# Grove_-_BLE_v1_0.net
KiCad netlist of a schematic drawn in EAGLE
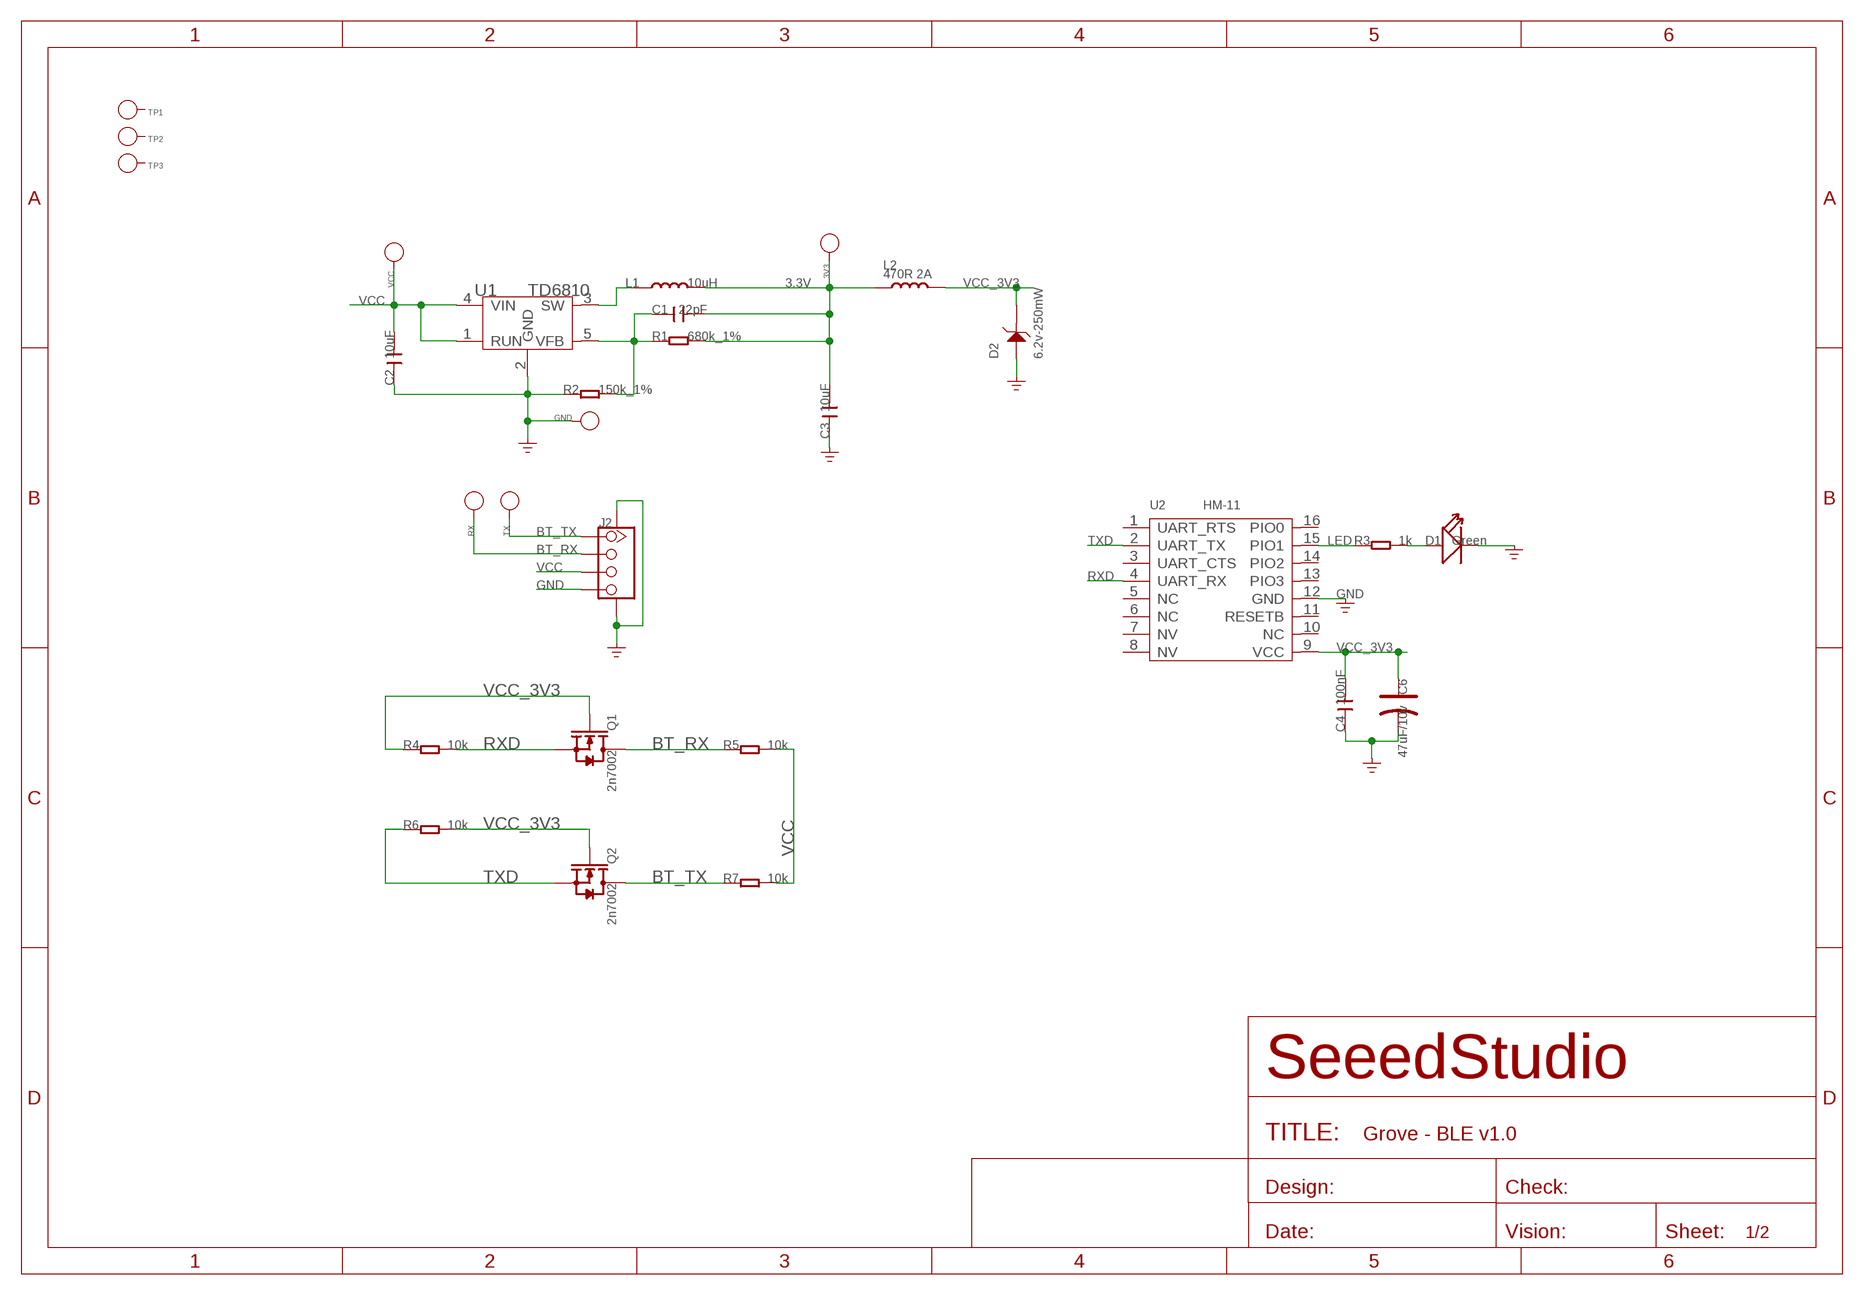
[diagram p0: schematic, sheet 1]
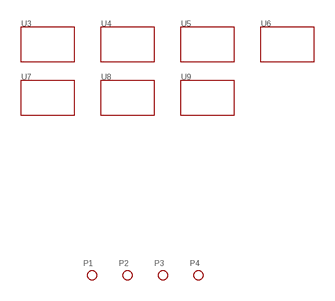
[diagram p1: schematic, sheet 2]

(export (version "E")
  (design (tool "Eeschema 10.0.6"))
  (components
    (comp (ref "P1")
      (value "PAD-MARK")
      (footprint "eagle-import:ROUND-MARK-1.0")
      (fields (field (name "PARTNO") "DNP"))
      (libsource (lib "eagle-import") (part "PAD-MARK"))
    )
    (comp (ref "P2")
      (value "PAD-MARK")
      (footprint "eagle-import:ROUND-MARK-1.0")
      (fields (field (name "PARTNO") "DNP"))
      (libsource (lib "eagle-import") (part "PAD-MARK"))
    )
    (comp (ref "P3")
      (value "PAD-MARK")
      (footprint "eagle-import:ROUND-MARK-1.0")
      (fields (field (name "PARTNO") "DNP"))
      (libsource (lib "eagle-import") (part "PAD-MARK"))
    )
    (comp (ref "P4")
      (value "PAD-MARK")
      (footprint "eagle-import:ROUND-MARK-1.0")
      (fields (field (name "PARTNO") "DNP"))
      (libsource (lib "eagle-import") (part "PAD-MARK"))
    )
    (comp (ref "U3")
      (value "TWIG'2U'")
      (footprint "eagle-import:GROVE-TEST-PLATFORM")
      (libsource (lib "eagle-import") (part "TWIG'2U'"))
    )
    (comp (ref "U4")
      (value "TWIG'2U'")
      (footprint "eagle-import:GROVE-TEST-PLATFORM")
      (libsource (lib "eagle-import") (part "TWIG'2U'"))
    )
    (comp (ref "U5")
      (value "TWIG'2U'")
      (footprint "eagle-import:GROVE-TEST-PLATFORM")
      (libsource (lib "eagle-import") (part "TWIG'2U'"))
    )
    (comp (ref "U6")
      (value "TWIG'2U'")
      (footprint "eagle-import:GROVE-TEST-PLATFORM")
      (libsource (lib "eagle-import") (part "TWIG'2U'"))
    )
    (comp (ref "U7")
      (value "TWIG'2U'")
      (footprint "eagle-import:GROVE-TEST-PLATFORM")
      (libsource (lib "eagle-import") (part "TWIG'2U'"))
    )
    (comp (ref "U8")
      (value "TWIG'2U'")
      (footprint "eagle-import:GROVE-TEST-PLATFORM")
      (libsource (lib "eagle-import") (part "TWIG'2U'"))
    )
    (comp (ref "U9")
      (value "TWIG'2U'")
      (footprint "eagle-import:GROVE-TEST-PLATFORM")
      (libsource (lib "eagle-import") (part "TWIG'2U'"))
    )
    (comp (ref "3V3")
      (value "PAD-TEST-POINT'4545'")
      (footprint "eagle-import:TP_4545")
      (fields (field (name "PARTNO") "DNP"))
      (libsource (lib "eagle-import") (part "PAD-TEST-POINT'4545'"))
    )
    (comp (ref "C1")
      (value "22pF")
      (footprint "eagle-import:C0603")
      (libsource (lib "eagle-import") (part "C-0603"))
    )
    (comp (ref "C2")
      (value "10uF")
      (footprint "eagle-import:C0805")
      (libsource (lib "eagle-import") (part "C-0805"))
    )
    (comp (ref "C3")
      (value "10uF")
      (footprint "eagle-import:C0805")
      (libsource (lib "eagle-import") (part "C-0805"))
    )
    (comp (ref "C4")
      (value "100nF")
      (footprint "eagle-import:C0603")
      (libsource (lib "eagle-import") (part "C-0603"))
    )
    (comp (ref "C6")
      (value "47uF/10v")
      (footprint "eagle-import:AVX-B")
      (libsource (lib "eagle-import") (part "CAP-AVX-B"))
    )
    (comp (ref "D1")
      (value "Green")
      (footprint "eagle-import:LED-0603")
      (libsource (lib "eagle-import") (part "LED'0603'"))
    )
    (comp (ref "D2")
      (value "6.2v-250mW")
      (footprint "eagle-import:SOD123-2.7X1.6")
      (libsource (lib "eagle-import") (part "D-ESD-2P'CESD5V0D1'"))
    )
    (comp (ref "GND")
      (value "PAD-TEST-POINT'4545'")
      (footprint "eagle-import:TP_4545")
      (fields (field (name "PARTNO") "DNP"))
      (libsource (lib "eagle-import") (part "PAD-TEST-POINT'4545'"))
    )
    (comp (ref "J2")
      (value "TWIG-4P-2.0-SMD-FEMALE-REINFORCE'DD'")
      (footprint "eagle-import:4P-SMD-2.0")
      (libsource (lib "eagle-import") (part "TWIG-4P-2.0-SMD-FEMALE-REINFORCE'DD'"))
    )
    (comp (ref "L1")
      (value "10uH")
      (footprint "eagle-import:1813")
      (libsource (lib "eagle-import") (part "L'1813'"))
    )
    (comp (ref "L2")
      (value "470R 2A")
      (footprint "eagle-import:L0805")
      (libsource (lib "eagle-import") (part "L'0805'"))
    )
    (comp (ref "Q1")
      (value "2n7002")
      (footprint "eagle-import:SOT23")
      (libsource (lib "eagle-import") (part "MOSFET-N'SOT23'"))
    )
    (comp (ref "Q2")
      (value "2n7002")
      (footprint "eagle-import:SOT23")
      (libsource (lib "eagle-import") (part "MOSFET-N'SOT23'"))
    )
    (comp (ref "R1")
      (value "680k_1%")
      (footprint "eagle-import:0603@1")
      (libsource (lib "eagle-import") (part "005-R0603"))
    )
    (comp (ref "R2")
      (value "150k_1%")
      (footprint "eagle-import:0603@1")
      (libsource (lib "eagle-import") (part "005-R0603"))
    )
    (comp (ref "R3")
      (value "1k")
      (footprint "eagle-import:R0603")
      (libsource (lib "eagle-import") (part "R-0603"))
    )
    (comp (ref "R4")
      (value "10k")
      (footprint "eagle-import:R0603")
      (libsource (lib "eagle-import") (part "R-0603"))
    )
    (comp (ref "R5")
      (value "10k")
      (footprint "eagle-import:R0603")
      (libsource (lib "eagle-import") (part "R-0603"))
    )
    (comp (ref "R6")
      (value "10k")
      (footprint "eagle-import:R0603")
      (libsource (lib "eagle-import") (part "R-0603"))
    )
    (comp (ref "R7")
      (value "10k")
      (footprint "eagle-import:R0603")
      (libsource (lib "eagle-import") (part "R-0603"))
    )
    (comp (ref "RX")
      (value "PAD-TEST-POINT'4545'")
      (footprint "eagle-import:TP_4545")
      (fields (field (name "PARTNO") "DNP"))
      (libsource (lib "eagle-import") (part "PAD-TEST-POINT'4545'"))
    )
    (comp (ref "TP1")
      (value "PAD-TEST-POINT'4545'")
      (footprint "eagle-import:TP_4545")
      (fields (field (name "PARTNO") "DNP"))
      (libsource (lib "eagle-import") (part "PAD-TEST-POINT'4545'"))
    )
    (comp (ref "TP2")
      (value "PAD-TEST-POINT'4545'")
      (footprint "eagle-import:TP_4545")
      (fields (field (name "PARTNO") "DNP"))
      (libsource (lib "eagle-import") (part "PAD-TEST-POINT'4545'"))
    )
    (comp (ref "TP3")
      (value "PAD-TEST-POINT'4545'")
      (footprint "eagle-import:TP_4545")
      (fields (field (name "PARTNO") "DNP"))
      (libsource (lib "eagle-import") (part "PAD-TEST-POINT'4545'"))
    )
    (comp (ref "TX")
      (value "PAD-TEST-POINT'4545'")
      (footprint "eagle-import:TP_4545")
      (fields (field (name "PARTNO") "DNP"))
      (libsource (lib "eagle-import") (part "PAD-TEST-POINT'4545'"))
    )
    (comp (ref "U1")
      (value "TD6810")
      (footprint "eagle-import:SOT23-5")
      (libsource (lib "eagle-import") (part "TD6810'TSOT23-5'"))
    )
    (comp (ref "U2")
      (value "HM-11")
      (footprint "eagle-import:16P-18.5X13.5X0.8")
      (libsource (lib "eagle-import") (part "HM-11"))
    )
    (comp (ref "VCC")
      (value "PAD-TEST-POINT'4545'")
      (footprint "eagle-import:TP_4545")
      (fields (field (name "PARTNO") "DNP"))
      (libsource (lib "eagle-import") (part "PAD-TEST-POINT'4545'"))
    )
  )
  (nets
    (net (code "1") (name "3.3V") (class "Default")
      (node (ref "3V3") (pin "T") (pinfunction "T_T") (pintype "bidirectional"))
      (node (ref "C1") (pin "2") (pinfunction "2_2") (pintype "passive"))
      (node (ref "C3") (pin "2") (pinfunction "2_2") (pintype "passive"))
      (node (ref "L1") (pin "2") (pinfunction "2_2") (pintype "passive"))
      (node (ref "L2") (pin "1") (pinfunction "1_1") (pintype "passive"))
      (node (ref "R1") (pin "2") (pinfunction "2_2") (pintype "passive"))
    )
    (net (code "2") (name "BT_RX") (class "Default")
      (node (ref "J2") (pin "2") (pinfunction "2_2") (pintype "bidirectional"))
      (node (ref "Q1") (pin "3") (pinfunction "D_3") (pintype "passive"))
      (node (ref "R5") (pin "1") (pinfunction "1_1") (pintype "passive"))
      (node (ref "RX") (pin "T") (pinfunction "T_T") (pintype "bidirectional"))
    )
    (net (code "3") (name "BT_TX") (class "Default")
      (node (ref "J2") (pin "1") (pinfunction "1_1") (pintype "bidirectional"))
      (node (ref "Q2") (pin "3") (pinfunction "D_3") (pintype "passive"))
      (node (ref "R7") (pin "1") (pinfunction "1_1") (pintype "passive"))
      (node (ref "TX") (pin "T") (pinfunction "T_T") (pintype "bidirectional"))
    )
    (net (code "4") (name "GND") (class "Default")
      (node (ref "C2") (pin "1") (pinfunction "1_1") (pintype "passive"))
      (node (ref "C3") (pin "1") (pinfunction "1_1") (pintype "passive"))
      (node (ref "C4") (pin "1") (pinfunction "1_1") (pintype "passive"))
      (node (ref "C6") (pin "-") (pinfunction "-_-") (pintype "passive"))
      (node (ref "D1") (pin "-") (pinfunction "-_-") (pintype "passive"))
      (node (ref "D2") (pin "1") (pinfunction "1_1") (pintype "bidirectional"))
      (node (ref "GND") (pin "T") (pinfunction "T_T") (pintype "bidirectional"))
      (node (ref "J2") (pin "4") (pinfunction "4_4") (pintype "bidirectional"))
      (node (ref "J2") (pin "SS1") (pinfunction "SS1_SS1") (pintype "bidirectional"))
      (node (ref "J2") (pin "SS2") (pinfunction "SS2_SS2") (pintype "bidirectional"))
      (node (ref "R2") (pin "1") (pinfunction "1_1") (pintype "passive"))
      (node (ref "U1") (pin "2") (pinfunction "GND_2") (pintype "power_in"))
      (node (ref "U2") (pin "12") (pinfunction "GND_12") (pintype "bidirectional"))
    )
    (net (code "5") (name "LED") (class "Default")
      (node (ref "R3") (pin "1") (pinfunction "1_1") (pintype "passive"))
      (node (ref "U2") (pin "15") (pinfunction "PIO1_15") (pintype "bidirectional"))
    )
    (net (code "6") (name "Net-(D1-Pad+)") (class "Default")
      (node (ref "D1") (pin "+") (pinfunction "+_+") (pintype "passive"))
      (node (ref "R3") (pin "2") (pinfunction "2_2") (pintype "passive"))
    )
    (net (code "7") (name "Net-(U1-SW)") (class "Default")
      (node (ref "L1") (pin "1") (pinfunction "1_1") (pintype "passive"))
      (node (ref "U1") (pin "3") (pinfunction "SW_3") (pintype "bidirectional"))
    )
    (net (code "8") (name "Net-(U1-VFB)") (class "Default")
      (node (ref "C1") (pin "1") (pinfunction "1_1") (pintype "passive"))
      (node (ref "R1") (pin "1") (pinfunction "1_1") (pintype "passive"))
      (node (ref "R2") (pin "2") (pinfunction "2_2") (pintype "passive"))
      (node (ref "U1") (pin "5") (pinfunction "VFB_5") (pintype "input"))
    )
    (net (code "9") (name "RXD") (class "Default")
      (node (ref "Q1") (pin "2") (pinfunction "S_2") (pintype "passive"))
      (node (ref "R4") (pin "2") (pinfunction "2_2") (pintype "passive"))
      (node (ref "U2") (pin "4") (pinfunction "UART_RX_4") (pintype "bidirectional"))
    )
    (net (code "10") (name "TXD") (class "Default")
      (node (ref "Q2") (pin "2") (pinfunction "S_2") (pintype "passive"))
      (node (ref "R6") (pin "1") (pinfunction "1_1") (pintype "passive"))
      (node (ref "U2") (pin "2") (pinfunction "UART_TX_2") (pintype "bidirectional"))
    )
    (net (code "11") (name "VCC") (class "Default")
      (node (ref "C2") (pin "2") (pinfunction "2_2") (pintype "passive"))
      (node (ref "J2") (pin "3") (pinfunction "3_3") (pintype "bidirectional"))
      (node (ref "R5") (pin "2") (pinfunction "2_2") (pintype "passive"))
      (node (ref "R7") (pin "2") (pinfunction "2_2") (pintype "passive"))
      (node (ref "U1") (pin "1") (pinfunction "RUN_1") (pintype "bidirectional"))
      (node (ref "U1") (pin "4") (pinfunction "VIN_4") (pintype "input"))
      (node (ref "VCC") (pin "T") (pinfunction "T_T") (pintype "bidirectional"))
    )
    (net (code "12") (name "VCC_3V3") (class "Default")
      (node (ref "C4") (pin "2") (pinfunction "2_2") (pintype "passive"))
      (node (ref "C6") (pin "+") (pinfunction "+_+") (pintype "passive"))
      (node (ref "D2") (pin "2") (pinfunction "2_2") (pintype "bidirectional"))
      (node (ref "L2") (pin "2") (pinfunction "2_2") (pintype "passive"))
      (node (ref "Q1") (pin "1") (pinfunction "G_1") (pintype "passive"))
      (node (ref "Q2") (pin "1") (pinfunction "G_1") (pintype "passive"))
      (node (ref "R4") (pin "1") (pinfunction "1_1") (pintype "passive"))
      (node (ref "R6") (pin "2") (pinfunction "2_2") (pintype "passive"))
      (node (ref "U2") (pin "9") (pinfunction "VCC_9") (pintype "bidirectional"))
    )
    (net (code "13") (name "unconnected-(TP1-PadT)") (class "Default")
      (node (ref "TP1") (pin "T") (pinfunction "T_T") (pintype "bidirectional"))
    )
    (net (code "14") (name "unconnected-(TP2-PadT)") (class "Default")
      (node (ref "TP2") (pin "T") (pinfunction "T_T") (pintype "bidirectional"))
    )
    (net (code "15") (name "unconnected-(TP3-PadT)") (class "Default")
      (node (ref "TP3") (pin "T") (pinfunction "T_T") (pintype "bidirectional"))
    )
    (net (code "16") (name "unconnected-(U2-NC-Pad5)") (class "Default")
      (node (ref "U2") (pin "5") (pinfunction "NC_5") (pintype "bidirectional"))
    )
    (net (code "17") (name "unconnected-(U2-NC-Pad6)") (class "Default")
      (node (ref "U2") (pin "6") (pinfunction "NC_6") (pintype "bidirectional"))
    )
    (net (code "18") (name "unconnected-(U2-NC-Pad10)") (class "Default")
      (node (ref "U2") (pin "10") (pinfunction "NC_10") (pintype "bidirectional"))
    )
    (net (code "19") (name "unconnected-(U2-NV-Pad7)") (class "Default")
      (node (ref "U2") (pin "7") (pinfunction "NV_7") (pintype "bidirectional"))
    )
    (net (code "20") (name "unconnected-(U2-NV-Pad8)") (class "Default")
      (node (ref "U2") (pin "8") (pinfunction "NV_8") (pintype "bidirectional"))
    )
    (net (code "21") (name "unconnected-(U2-PIO0-Pad16)") (class "Default")
      (node (ref "U2") (pin "16") (pinfunction "PIO0_16") (pintype "bidirectional"))
    )
    (net (code "22") (name "unconnected-(U2-PIO2-Pad14)") (class "Default")
      (node (ref "U2") (pin "14") (pinfunction "PIO2_14") (pintype "bidirectional"))
    )
    (net (code "23") (name "unconnected-(U2-PIO3-Pad13)") (class "Default")
      (node (ref "U2") (pin "13") (pinfunction "PIO3_13") (pintype "bidirectional"))
    )
    (net (code "24") (name "unconnected-(U2-RESETB-Pad11)") (class "Default")
      (node (ref "U2") (pin "11") (pinfunction "RESETB_11") (pintype "bidirectional"))
    )
    (net (code "25") (name "unconnected-(U2-UART_CTS-Pad3)") (class "Default")
      (node (ref "U2") (pin "3") (pinfunction "UART_CTS_3") (pintype "bidirectional"))
    )
    (net (code "26") (name "unconnected-(U2-UART_RTS-Pad1)") (class "Default")
      (node (ref "U2") (pin "1") (pinfunction "UART_RTS_1") (pintype "bidirectional"))
    )
  )
)
